# rk097_-_breakout.net
KiCad netlist of a schematic drawn in EAGLE
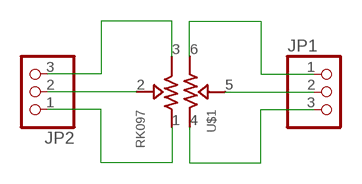
[diagram p0: schematic, sheet 1]

(export (version "E")
  (design (tool "Eeschema 10.0.6"))
  (components
    (comp (ref "JP1")
      (value "PINHD-1X3")
      (footprint "eagle-import:1X03")
      (libsource (lib "eagle-import") (part "PINHD-1X3"))
    )
    (comp (ref "JP2")
      (value "PINHD-1X3")
      (footprint "eagle-import:1X03")
      (libsource (lib "eagle-import") (part "PINHD-1X3"))
    )
    (comp (ref "U$1")
      (value "RK097")
      (footprint "eagle-import:RK097")
      (libsource (lib "eagle-import") (part "RK097"))
    )
  )
  (nets
    (net (code "1") (name "Net-(JP1-Pad1)") (class "Default")
      (node (ref "JP1") (pin "1") (pinfunction "1_1") (pintype "passive"))
      (node (ref "U$1") (pin "6") (pinfunction "6_6") (pintype "bidirectional"))
    )
    (net (code "2") (name "Net-(JP1-Pad2)") (class "Default")
      (node (ref "JP1") (pin "2") (pinfunction "2_2") (pintype "passive"))
      (node (ref "U$1") (pin "5") (pinfunction "5_5") (pintype "bidirectional"))
    )
    (net (code "3") (name "Net-(JP1-Pad3)") (class "Default")
      (node (ref "JP1") (pin "3") (pinfunction "3_3") (pintype "passive"))
      (node (ref "U$1") (pin "4") (pinfunction "4_4") (pintype "bidirectional"))
    )
    (net (code "4") (name "Net-(JP2-Pad1)") (class "Default")
      (node (ref "JP2") (pin "1") (pinfunction "1_1") (pintype "passive"))
      (node (ref "U$1") (pin "1") (pinfunction "1_1") (pintype "bidirectional"))
    )
    (net (code "5") (name "Net-(JP2-Pad2)") (class "Default")
      (node (ref "JP2") (pin "2") (pinfunction "2_2") (pintype "passive"))
      (node (ref "U$1") (pin "2") (pinfunction "2_2") (pintype "bidirectional"))
    )
    (net (code "6") (name "Net-(JP2-Pad3)") (class "Default")
      (node (ref "JP2") (pin "3") (pinfunction "3_3") (pintype "passive"))
      (node (ref "U$1") (pin "3") (pinfunction "3_3") (pintype "bidirectional"))
    )
  )
)
